# modular_expansion_system_graphics_and_so.net
KiCad netlist of a schematic drawn in EAGLE
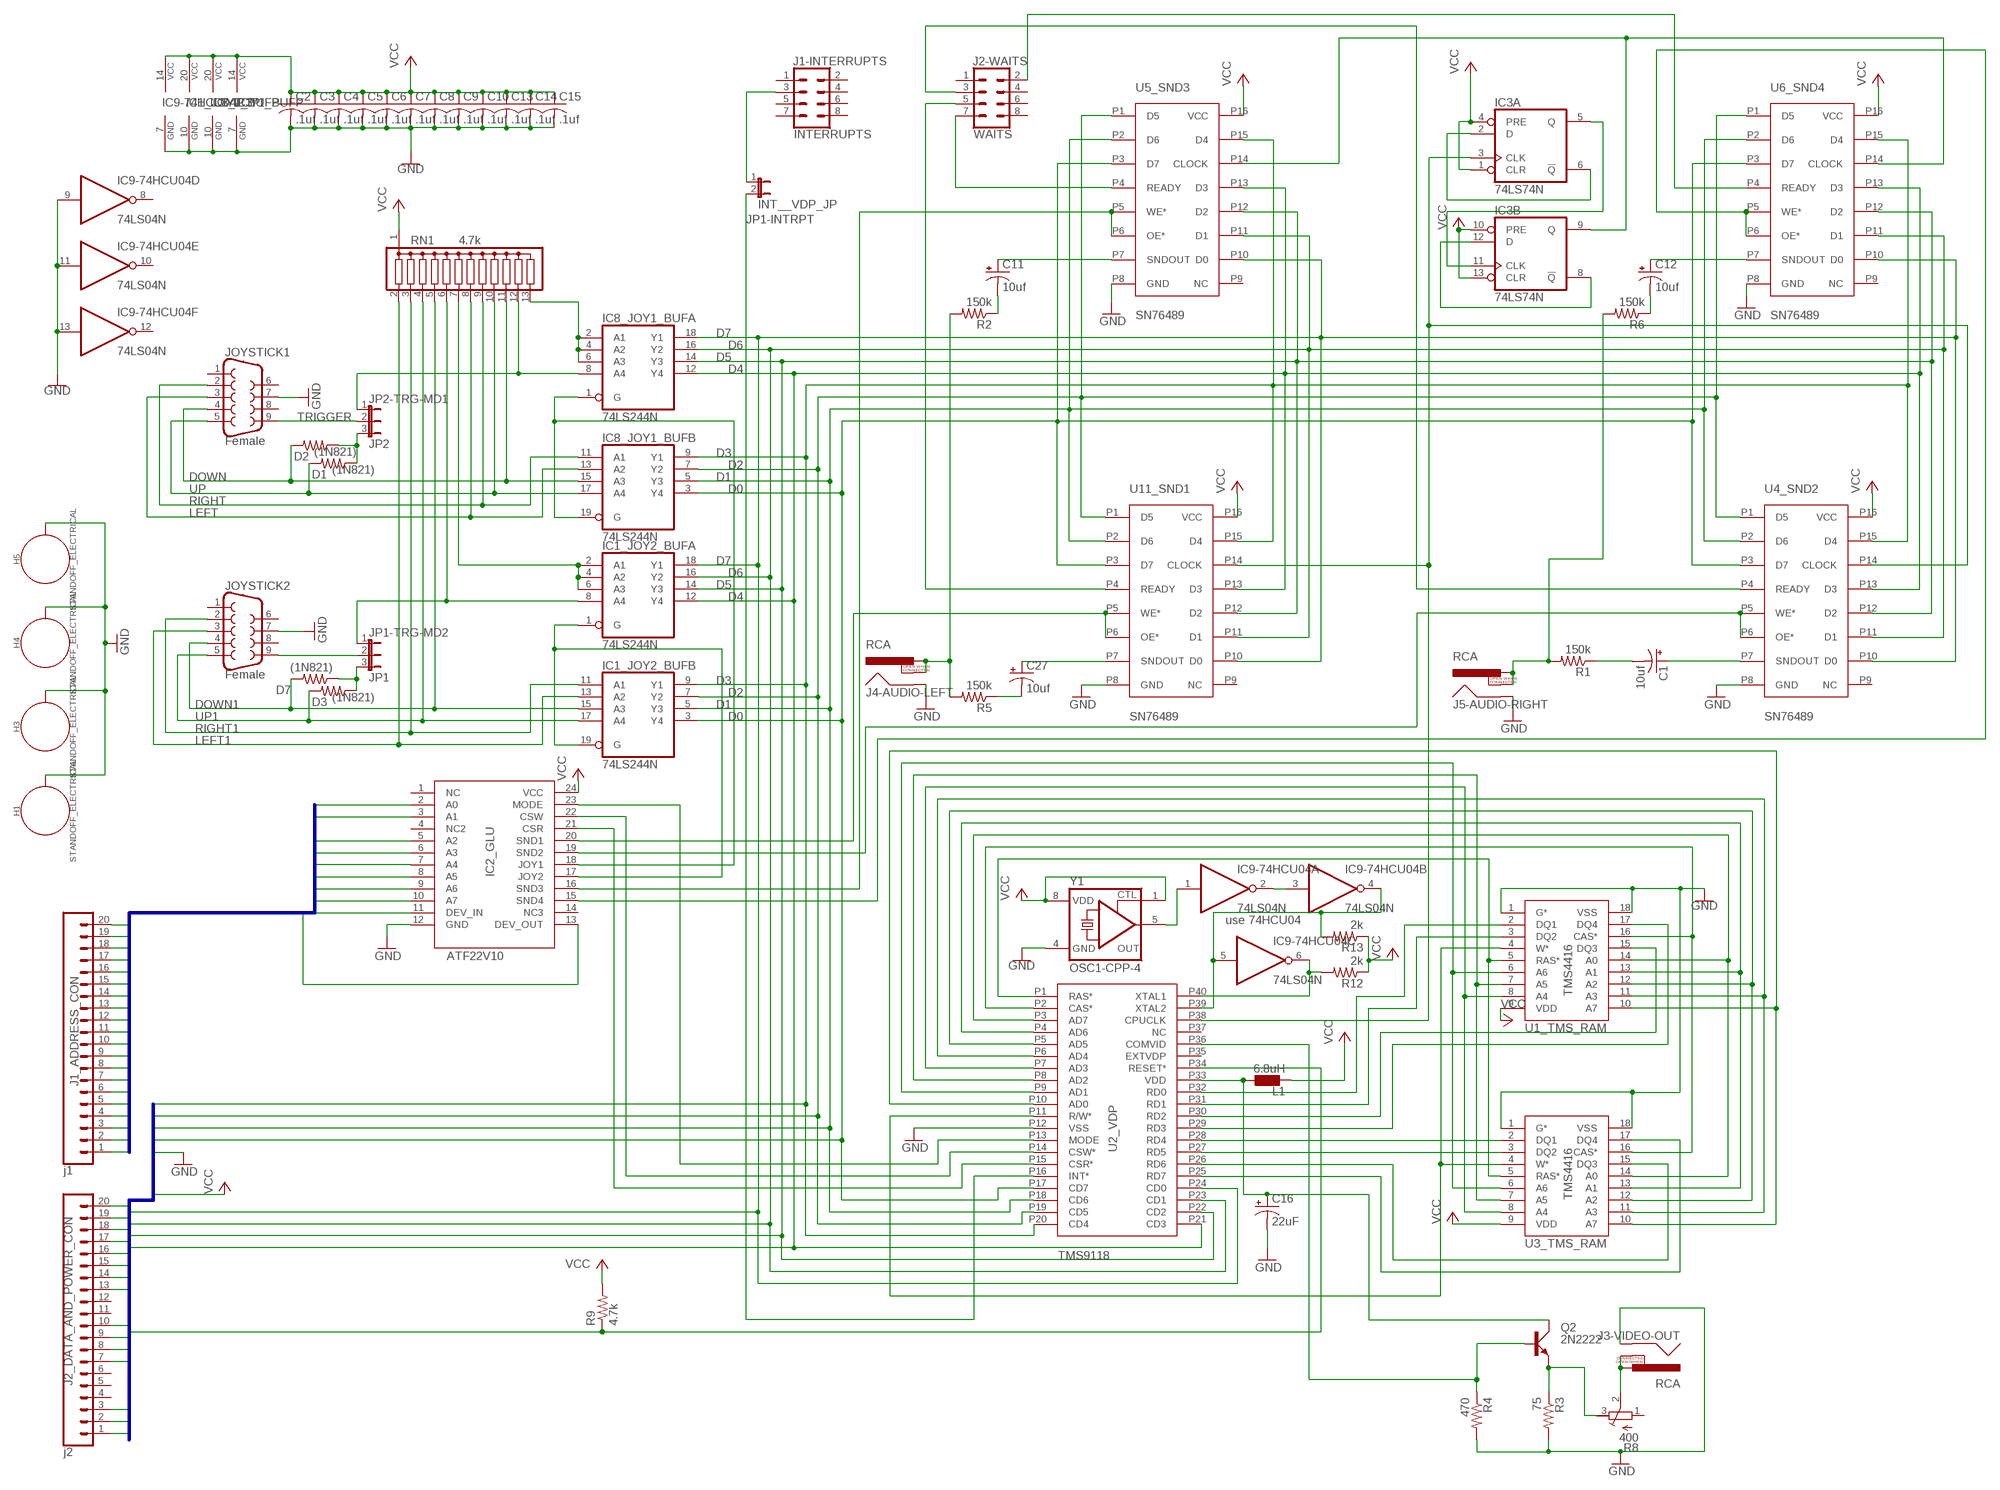
[diagram p0: schematic, sheet 1]

(export (version "E")
  (design (tool "Eeschema 10.0.6"))
  (components
    (comp (ref "C1")
      (value "10uf")
      (footprint "eagle-import:E2,5-6")
      (libsource (lib "eagle-import") (part "CPOL-USE2.5-6"))
    )
    (comp (ref "C2")
      (value ".1uf")
      (footprint "eagle-import:C025-024X044")
      (libsource (lib "eagle-import") (part "C-US025-024X044"))
    )
    (comp (ref "C3")
      (value ".1uf")
      (footprint "eagle-import:C025-024X044")
      (libsource (lib "eagle-import") (part "C-US025-024X044"))
    )
    (comp (ref "C4")
      (value ".1uf")
      (footprint "eagle-import:C025-024X044")
      (libsource (lib "eagle-import") (part "C-US025-024X044"))
    )
    (comp (ref "C5")
      (value ".1uf")
      (footprint "eagle-import:C025-024X044")
      (libsource (lib "eagle-import") (part "C-US025-024X044"))
    )
    (comp (ref "C6")
      (value ".1uf")
      (footprint "eagle-import:C025-024X044")
      (libsource (lib "eagle-import") (part "C-US025-024X044"))
    )
    (comp (ref "C7")
      (value ".1uf")
      (footprint "eagle-import:C025-024X044")
      (libsource (lib "eagle-import") (part "C-US025-024X044"))
    )
    (comp (ref "C8")
      (value ".1uf")
      (footprint "eagle-import:C025-024X044")
      (libsource (lib "eagle-import") (part "C-US025-024X044"))
    )
    (comp (ref "C9")
      (value ".1uf")
      (footprint "eagle-import:C025-024X044")
      (libsource (lib "eagle-import") (part "C-US025-024X044"))
    )
    (comp (ref "C10")
      (value ".1uf")
      (footprint "eagle-import:C025-024X044")
      (libsource (lib "eagle-import") (part "C-US025-024X044"))
    )
    (comp (ref "C11")
      (value "10uf")
      (footprint "eagle-import:E2,5-6")
      (libsource (lib "eagle-import") (part "CPOL-USE2.5-6"))
    )
    (comp (ref "C12")
      (value "10uf")
      (footprint "eagle-import:E2,5-6")
      (libsource (lib "eagle-import") (part "CPOL-USE2.5-6"))
    )
    (comp (ref "C13")
      (value ".1uf")
      (footprint "eagle-import:C025-024X044")
      (libsource (lib "eagle-import") (part "C-US025-024X044"))
    )
    (comp (ref "C14")
      (value ".1uf")
      (footprint "eagle-import:C025-024X044")
      (libsource (lib "eagle-import") (part "C-US025-024X044"))
    )
    (comp (ref "C15")
      (value ".1uf")
      (footprint "eagle-import:C025-024X044")
      (libsource (lib "eagle-import") (part "C-US025-024X044"))
    )
    (comp (ref "C16")
      (value "22uF")
      (footprint "eagle-import:E2,5-5")
      (libsource (lib "eagle-import") (part "CPOL-USE2.5-5"))
    )
    (comp (ref "C27")
      (value "10uf")
      (footprint "eagle-import:E2,5-6")
      (libsource (lib "eagle-import") (part "CPOL-USE2.5-6"))
    )
    (comp (ref "D1")
      (value "(1N821)")
      (footprint "eagle-import:0204V")
      (libsource (lib "eagle-import") (part "R-US_0204/2V"))
    )
    (comp (ref "D2")
      (value "(1N821)")
      (footprint "eagle-import:0204V")
      (libsource (lib "eagle-import") (part "R-US_0204/2V"))
    )
    (comp (ref "D3")
      (value "(1N821)")
      (footprint "eagle-import:0204V")
      (libsource (lib "eagle-import") (part "R-US_0204/2V"))
    )
    (comp (ref "D7")
      (value "(1N821)")
      (footprint "eagle-import:0204V")
      (libsource (lib "eagle-import") (part "R-US_0204/2V"))
    )
    (comp (ref "H1")
      (value "STANDOFF_ELECTRICAL")
      (footprint "eagle-import:STANDOFF-ELECTRICAL")
      (libsource (lib "eagle-import") (part "STANDOFF_ELECTRICAL"))
    )
    (comp (ref "H3")
      (value "STANDOFF_ELECTRICAL")
      (footprint "eagle-import:STANDOFF-ELECTRICAL")
      (libsource (lib "eagle-import") (part "STANDOFF_ELECTRICAL"))
    )
    (comp (ref "H4")
      (value "STANDOFF_ELECTRICAL")
      (footprint "eagle-import:STANDOFF-ELECTRICAL")
      (libsource (lib "eagle-import") (part "STANDOFF_ELECTRICAL"))
    )
    (comp (ref "H5")
      (value "STANDOFF_ELECTRICAL")
      (footprint "eagle-import:STANDOFF-ELECTRICAL")
      (libsource (lib "eagle-import") (part "STANDOFF_ELECTRICAL"))
    )
    (comp (ref "IC1_JOY2_BUF")
      (value "74LS244N")
      (footprint "eagle-import:DIL20")
      (libsource (lib "eagle-import") (part "74244NLS"))
    )
    (comp (ref "IC2_GLU")
      (value "ATF22V10")
      (footprint "eagle-import:DIP24SKI")
      (libsource (lib "eagle-import") (part "TRS80MXS_DECODER"))
    )
    (comp (ref "IC3")
      (value "74LS74N")
      (footprint "eagle-import:DIL14")
      (libsource (lib "eagle-import") (part "7474NLS"))
    )
    (comp (ref "IC8_JOY1_BUF")
      (value "74LS244N")
      (footprint "eagle-import:DIL20")
      (libsource (lib "eagle-import") (part "74244NLS"))
    )
    (comp (ref "IC9-74HCU04")
      (value "74LS04N")
      (footprint "eagle-import:DIL14")
      (libsource (lib "eagle-import") (part "7404NLS"))
    )
    (comp (ref "J1-INTERRUPTS")
      (value "INTERRUPTS")
      (footprint "eagle-import:2X4")
      (libsource (lib "eagle-import") (part "CONN_04X2"))
    )
    (comp (ref "J1_ADDRESS_CON")
      (value "j1")
      (footprint "eagle-import:1X20")
      (libsource (lib "eagle-import") (part "CONN_20"))
    )
    (comp (ref "J2-WAITS")
      (value "WAITS")
      (footprint "eagle-import:2X4")
      (libsource (lib "eagle-import") (part "CONN_04X2"))
    )
    (comp (ref "J2_DATA_AND_POWER_CON")
      (value "j2")
      (footprint "eagle-import:1X20")
      (libsource (lib "eagle-import") (part "CONN_20"))
    )
    (comp (ref "J3-VIDEO-OUT")
      (value "RCA")
      (footprint "eagle-import:RCA")
      (libsource (lib "eagle-import") (part "RCA"))
    )
    (comp (ref "J4-AUDIO-LEFT")
      (value "RCA")
      (footprint "eagle-import:RCA")
      (libsource (lib "eagle-import") (part "RCA"))
    )
    (comp (ref "J5-AUDIO-RIGHT")
      (value "RCA")
      (footprint "eagle-import:RCA")
      (libsource (lib "eagle-import") (part "RCA"))
    )
    (comp (ref "JOYSTICK1")
      (value "Female")
      (footprint "eagle-import:DB9")
      (libsource (lib "eagle-import") (part "DB9FEMALE"))
    )
    (comp (ref "JOYSTICK2")
      (value "Female")
      (footprint "eagle-import:DB9")
      (libsource (lib "eagle-import") (part "DB9FEMALE"))
    )
    (comp (ref "JP1-INTRPT")
      (value "INT__VDP_JP")
      (footprint "eagle-import:JP1")
      (libsource (lib "eagle-import") (part "JP1E"))
    )
    (comp (ref "JP1-TRG-MD2")
      (value "JP1")
      (footprint "eagle-import:JP2")
      (libsource (lib "eagle-import") (part "JP2E"))
    )
    (comp (ref "JP2-TRG-MD1")
      (value "JP2")
      (footprint "eagle-import:JP2")
      (libsource (lib "eagle-import") (part "JP2E"))
    )
    (comp (ref "L1")
      (value "6.8uH")
      (footprint "eagle-import:0207_10")
      (libsource (lib "eagle-import") (part "L0207/10"))
    )
    (comp (ref "Q2")
      (value "2N2222")
      (footprint "eagle-import:TO18A")
      (libsource (lib "eagle-import") (part "2N2222"))
    )
    (comp (ref "R1")
      (value "150k")
      (footprint "eagle-import:0207_2V")
      (libsource (lib "eagle-import") (part "resistor_348_R-US_0207/2V"))
    )
    (comp (ref "R2")
      (value "150k")
      (footprint "eagle-import:0207_2V")
      (libsource (lib "eagle-import") (part "resistor_348_R-US_0207/2V"))
    )
    (comp (ref "R3")
      (value "75")
      (footprint "eagle-import:0207_2V")
      (libsource (lib "eagle-import") (part "resistor_348_R-US_0207/2V"))
    )
    (comp (ref "R4")
      (value "470")
      (footprint "eagle-import:0207_2V")
      (libsource (lib "eagle-import") (part "resistor_348_R-US_0207/2V"))
    )
    (comp (ref "R5")
      (value "150k")
      (footprint "eagle-import:0207_2V")
      (libsource (lib "eagle-import") (part "resistor_348_R-US_0207/2V"))
    )
    (comp (ref "R6")
      (value "150k")
      (footprint "eagle-import:0207_2V")
      (libsource (lib "eagle-import") (part "resistor_348_R-US_0207/2V"))
    )
    (comp (ref "R8")
      (value "400")
      (footprint "eagle-import:RTRIM64W")
      (libsource (lib "eagle-import") (part "R-TRIMM64W"))
    )
    (comp (ref "R9")
      (value "4.7k")
      (footprint "eagle-import:0207_2V")
      (libsource (lib "eagle-import") (part "resistor_348_R-US_0207/2V"))
    )
    (comp (ref "R12")
      (value "2k")
      (footprint "eagle-import:0207_2V")
      (libsource (lib "eagle-import") (part "resistor_348_R-US_0207/2V"))
    )
    (comp (ref "R13")
      (value "2k")
      (footprint "eagle-import:0207_2V")
      (libsource (lib "eagle-import") (part "resistor_348_R-US_0207/2V"))
    )
    (comp (ref "RN1")
      (value "4.7k")
      (footprint "eagle-import:SIL13")
      (libsource (lib "eagle-import") (part "G12R"))
    )
    (comp (ref "U1_TMS_RAM")
      (value "TMS4416")
      (footprint "eagle-import:DIP18")
      (libsource (lib "eagle-import") (part "TMS4416"))
    )
    (comp (ref "U2_VDP")
      (value "TMS9118")
      (footprint "eagle-import:DIP40_MCU")
      (libsource (lib "eagle-import") (part "TMS9118"))
    )
    (comp (ref "U3_TMS_RAM")
      (value "TMS4416")
      (footprint "eagle-import:DIP18")
      (libsource (lib "eagle-import") (part "TMS4416"))
    )
    (comp (ref "U4_SND2")
      (value "SN76489")
      (footprint "eagle-import:DIP16")
      (libsource (lib "eagle-import") (part "SN76489"))
    )
    (comp (ref "U5_SND3")
      (value "SN76489")
      (footprint "eagle-import:DIP16")
      (libsource (lib "eagle-import") (part "SN76489"))
    )
    (comp (ref "U6_SND4")
      (value "SN76489")
      (footprint "eagle-import:DIP16")
      (libsource (lib "eagle-import") (part "SN76489"))
    )
    (comp (ref "U11_SND1")
      (value "SN76489")
      (footprint "eagle-import:DIP16")
      (libsource (lib "eagle-import") (part "SN76489"))
    )
    (comp (ref "Y1")
      (value "OSC1-CPP-4")
      (footprint "eagle-import:CPP-4")
      (libsource (lib "eagle-import") (part "OSC1-CPP-4"))
    )
  )
  (nets
    (net (code "1") (name "/A0") (class "Default")
      (node (ref "IC2_GLU") (pin "2") (pinfunction "A0_2") (pintype "bidirectional"))
      (node (ref "J1_ADDRESS_CON") (pin "1") (pinfunction "1_1") (pintype "passive"))
    )
    (net (code "2") (name "/A1") (class "Default")
      (node (ref "IC2_GLU") (pin "3") (pinfunction "A1_3") (pintype "bidirectional"))
      (node (ref "J1_ADDRESS_CON") (pin "2") (pinfunction "2_2") (pintype "passive"))
    )
    (net (code "3") (name "/A2") (class "Default")
      (node (ref "IC2_GLU") (pin "5") (pinfunction "A2_5") (pintype "bidirectional"))
      (node (ref "J1_ADDRESS_CON") (pin "3") (pinfunction "3_3") (pintype "passive"))
    )
    (net (code "4") (name "/A3") (class "Default")
      (node (ref "IC2_GLU") (pin "6") (pinfunction "A3_6") (pintype "bidirectional"))
      (node (ref "J1_ADDRESS_CON") (pin "4") (pinfunction "4_4") (pintype "passive"))
    )
    (net (code "5") (name "/A4") (class "Default")
      (node (ref "IC2_GLU") (pin "7") (pinfunction "A4_7") (pintype "bidirectional"))
      (node (ref "J1_ADDRESS_CON") (pin "5") (pinfunction "5_5") (pintype "passive"))
    )
    (net (code "6") (name "/A5") (class "Default")
      (node (ref "IC2_GLU") (pin "8") (pinfunction "A5_8") (pintype "bidirectional"))
      (node (ref "J1_ADDRESS_CON") (pin "6") (pinfunction "6_6") (pintype "passive"))
    )
    (net (code "7") (name "/A6") (class "Default")
      (node (ref "IC2_GLU") (pin "9") (pinfunction "A6_9") (pintype "bidirectional"))
      (node (ref "J1_ADDRESS_CON") (pin "7") (pinfunction "7_7") (pintype "passive"))
    )
    (net (code "8") (name "/A7") (class "Default")
      (node (ref "IC2_GLU") (pin "10") (pinfunction "A7_10") (pintype "bidirectional"))
      (node (ref "J1_ADDRESS_CON") (pin "8") (pinfunction "8_8") (pintype "passive"))
    )
    (net (code "9") (name "/D0") (class "Default")
      (node (ref "IC1_JOY2_BUF") (pin "3") (pinfunction "Y4_3") (pintype "tri_state"))
      (node (ref "IC8_JOY1_BUF") (pin "3") (pinfunction "Y4_3") (pintype "tri_state"))
      (node (ref "J2_DATA_AND_POWER_CON") (pin "20") (pinfunction "20_20") (pintype "passive"))
      (node (ref "U11_SND1") (pin "P3") (pinfunction "D7_P3") (pintype "bidirectional"))
      (node (ref "U2_VDP") (pin "P17") (pinfunction "CD7_P17") (pintype "bidirectional"))
      (node (ref "U4_SND2") (pin "P3") (pinfunction "D7_P3") (pintype "bidirectional"))
      (node (ref "U5_SND3") (pin "P3") (pinfunction "D7_P3") (pintype "bidirectional"))
      (node (ref "U6_SND4") (pin "P3") (pinfunction "D7_P3") (pintype "bidirectional"))
    )
    (net (code "10") (name "/D1") (class "Default")
      (node (ref "IC1_JOY2_BUF") (pin "5") (pinfunction "Y3_5") (pintype "tri_state"))
      (node (ref "IC8_JOY1_BUF") (pin "5") (pinfunction "Y3_5") (pintype "tri_state"))
      (node (ref "J2_DATA_AND_POWER_CON") (pin "19") (pinfunction "19_19") (pintype "passive"))
      (node (ref "U11_SND1") (pin "P2") (pinfunction "D6_P2") (pintype "bidirectional"))
      (node (ref "U2_VDP") (pin "P18") (pinfunction "CD6_P18") (pintype "bidirectional"))
      (node (ref "U4_SND2") (pin "P2") (pinfunction "D6_P2") (pintype "bidirectional"))
      (node (ref "U5_SND3") (pin "P2") (pinfunction "D6_P2") (pintype "bidirectional"))
      (node (ref "U6_SND4") (pin "P2") (pinfunction "D6_P2") (pintype "bidirectional"))
    )
    (net (code "11") (name "/D2") (class "Default")
      (node (ref "IC1_JOY2_BUF") (pin "7") (pinfunction "Y2_7") (pintype "tri_state"))
      (node (ref "IC8_JOY1_BUF") (pin "7") (pinfunction "Y2_7") (pintype "tri_state"))
      (node (ref "J2_DATA_AND_POWER_CON") (pin "18") (pinfunction "18_18") (pintype "passive"))
      (node (ref "U11_SND1") (pin "P1") (pinfunction "D5_P1") (pintype "bidirectional"))
      (node (ref "U2_VDP") (pin "P19") (pinfunction "CD5_P19") (pintype "bidirectional"))
      (node (ref "U4_SND2") (pin "P1") (pinfunction "D5_P1") (pintype "bidirectional"))
      (node (ref "U5_SND3") (pin "P1") (pinfunction "D5_P1") (pintype "bidirectional"))
      (node (ref "U6_SND4") (pin "P1") (pinfunction "D5_P1") (pintype "bidirectional"))
    )
    (net (code "12") (name "/D3") (class "Default")
      (node (ref "IC1_JOY2_BUF") (pin "9") (pinfunction "Y1_9") (pintype "tri_state"))
      (node (ref "IC8_JOY1_BUF") (pin "9") (pinfunction "Y1_9") (pintype "tri_state"))
      (node (ref "J2_DATA_AND_POWER_CON") (pin "17") (pinfunction "17_17") (pintype "passive"))
      (node (ref "U11_SND1") (pin "P15") (pinfunction "D4_P15") (pintype "bidirectional"))
      (node (ref "U2_VDP") (pin "P20") (pinfunction "CD4_P20") (pintype "bidirectional"))
      (node (ref "U4_SND2") (pin "P15") (pinfunction "D4_P15") (pintype "bidirectional"))
      (node (ref "U5_SND3") (pin "P15") (pinfunction "D4_P15") (pintype "bidirectional"))
      (node (ref "U6_SND4") (pin "P15") (pinfunction "D4_P15") (pintype "bidirectional"))
    )
    (net (code "13") (name "/D4") (class "Default")
      (node (ref "IC1_JOY2_BUF") (pin "12") (pinfunction "Y4_12") (pintype "tri_state"))
      (node (ref "IC8_JOY1_BUF") (pin "12") (pinfunction "Y4_12") (pintype "tri_state"))
      (node (ref "J2_DATA_AND_POWER_CON") (pin "16") (pinfunction "16_16") (pintype "passive"))
      (node (ref "U11_SND1") (pin "P13") (pinfunction "D3_P13") (pintype "bidirectional"))
      (node (ref "U2_VDP") (pin "P21") (pinfunction "CD3_P21") (pintype "bidirectional"))
      (node (ref "U4_SND2") (pin "P13") (pinfunction "D3_P13") (pintype "bidirectional"))
      (node (ref "U5_SND3") (pin "P13") (pinfunction "D3_P13") (pintype "bidirectional"))
      (node (ref "U6_SND4") (pin "P13") (pinfunction "D3_P13") (pintype "bidirectional"))
    )
    (net (code "14") (name "/D5") (class "Default")
      (node (ref "IC1_JOY2_BUF") (pin "14") (pinfunction "Y3_14") (pintype "tri_state"))
      (node (ref "IC8_JOY1_BUF") (pin "14") (pinfunction "Y3_14") (pintype "tri_state"))
      (node (ref "J2_DATA_AND_POWER_CON") (pin "15") (pinfunction "15_15") (pintype "passive"))
      (node (ref "U11_SND1") (pin "P12") (pinfunction "D2_P12") (pintype "bidirectional"))
      (node (ref "U2_VDP") (pin "P22") (pinfunction "CD2_P22") (pintype "bidirectional"))
      (node (ref "U4_SND2") (pin "P12") (pinfunction "D2_P12") (pintype "bidirectional"))
      (node (ref "U5_SND3") (pin "P12") (pinfunction "D2_P12") (pintype "bidirectional"))
      (node (ref "U6_SND4") (pin "P12") (pinfunction "D2_P12") (pintype "bidirectional"))
    )
    (net (code "15") (name "/D6") (class "Default")
      (node (ref "IC1_JOY2_BUF") (pin "16") (pinfunction "Y2_16") (pintype "tri_state"))
      (node (ref "IC8_JOY1_BUF") (pin "16") (pinfunction "Y2_16") (pintype "tri_state"))
      (node (ref "J2_DATA_AND_POWER_CON") (pin "14") (pinfunction "14_14") (pintype "passive"))
      (node (ref "U11_SND1") (pin "P11") (pinfunction "D1_P11") (pintype "bidirectional"))
      (node (ref "U2_VDP") (pin "P23") (pinfunction "CD1_P23") (pintype "bidirectional"))
      (node (ref "U4_SND2") (pin "P11") (pinfunction "D1_P11") (pintype "bidirectional"))
      (node (ref "U5_SND3") (pin "P11") (pinfunction "D1_P11") (pintype "bidirectional"))
      (node (ref "U6_SND4") (pin "P11") (pinfunction "D1_P11") (pintype "bidirectional"))
    )
    (net (code "16") (name "/D7") (class "Default")
      (node (ref "IC1_JOY2_BUF") (pin "18") (pinfunction "Y1_18") (pintype "tri_state"))
      (node (ref "IC8_JOY1_BUF") (pin "18") (pinfunction "Y1_18") (pintype "tri_state"))
      (node (ref "J2_DATA_AND_POWER_CON") (pin "13") (pinfunction "13_13") (pintype "passive"))
      (node (ref "U11_SND1") (pin "P10") (pinfunction "D0_P10") (pintype "bidirectional"))
      (node (ref "U2_VDP") (pin "P24") (pinfunction "CD0_P24") (pintype "bidirectional"))
      (node (ref "U4_SND2") (pin "P10") (pinfunction "D0_P10") (pintype "bidirectional"))
      (node (ref "U5_SND3") (pin "P10") (pinfunction "D0_P10") (pintype "bidirectional"))
      (node (ref "U6_SND4") (pin "P10") (pinfunction "D0_P10") (pintype "bidirectional"))
    )
    (net (code "17") (name "/DOWN") (class "Default")
      (node (ref "D2") (pin "2") (pinfunction "2_2") (pintype "passive"))
      (node (ref "IC8_JOY1_BUF") (pin "15") (pinfunction "A3_15") (pintype "input"))
      (node (ref "JOYSTICK1") (pin "4") (pinfunction "4_4") (pintype "passive"))
      (node (ref "RN1") (pin "11") (pinfunction "11_11") (pintype "passive"))
    )
    (net (code "18") (name "/DOWN1") (class "Default")
      (node (ref "D7") (pin "2") (pinfunction "2_2") (pintype "passive"))
      (node (ref "IC1_JOY2_BUF") (pin "15") (pinfunction "A3_15") (pintype "input"))
      (node (ref "JOYSTICK2") (pin "4") (pinfunction "4_4") (pintype "passive"))
      (node (ref "RN1") (pin "5") (pinfunction "5_5") (pintype "passive"))
    )
    (net (code "19") (name "/IN*") (class "Default")
      (node (ref "IC2_GLU") (pin "11") (pinfunction "DEV_IN_11") (pintype "bidirectional"))
      (node (ref "J1_ADDRESS_CON") (pin "17") (pinfunction "17_17") (pintype "passive"))
    )
    (net (code "20") (name "/LEFT") (class "Default")
      (node (ref "IC8_JOY1_BUF") (pin "13") (pinfunction "A2_13") (pintype "input"))
      (node (ref "JOYSTICK1") (pin "3") (pinfunction "3_3") (pintype "passive"))
      (node (ref "RN1") (pin "8") (pinfunction "8_8") (pintype "passive"))
    )
    (net (code "21") (name "/LEFT1") (class "Default")
      (node (ref "IC1_JOY2_BUF") (pin "13") (pinfunction "A2_13") (pintype "input"))
      (node (ref "JOYSTICK2") (pin "3") (pinfunction "3_3") (pintype "passive"))
      (node (ref "RN1") (pin "2") (pinfunction "2_2") (pintype "passive"))
    )
    (net (code "22") (name "/OUT*") (class "Default")
      (node (ref "IC2_GLU") (pin "13") (pinfunction "DEV_OUT_13") (pintype "bidirectional"))
      (node (ref "J1_ADDRESS_CON") (pin "18") (pinfunction "18_18") (pintype "passive"))
    )
    (net (code "23") (name "/RIGHT") (class "Default")
      (node (ref "IC8_JOY1_BUF") (pin "11") (pinfunction "A1_11") (pintype "input"))
      (node (ref "JOYSTICK1") (pin "2") (pinfunction "2_2") (pintype "passive"))
      (node (ref "RN1") (pin "9") (pinfunction "9_9") (pintype "passive"))
    )
    (net (code "24") (name "/RIGHT1") (class "Default")
      (node (ref "IC1_JOY2_BUF") (pin "11") (pinfunction "A1_11") (pintype "input"))
      (node (ref "JOYSTICK2") (pin "2") (pinfunction "2_2") (pintype "passive"))
      (node (ref "RN1") (pin "3") (pinfunction "3_3") (pintype "passive"))
    )
    (net (code "25") (name "/SYSRES*") (class "Default")
      (node (ref "J2_DATA_AND_POWER_CON") (pin "8") (pinfunction "8_8") (pintype "passive"))
      (node (ref "R9") (pin "1") (pinfunction "1_1") (pintype "passive"))
      (node (ref "U2_VDP") (pin "P34") (pinfunction "RESET*_P34") (pintype "bidirectional"))
    )
    (net (code "26") (name "/TRIGGER") (class "Default")
      (node (ref "JOYSTICK1") (pin "9") (pinfunction "9_9") (pintype "passive"))
      (node (ref "JP2-TRG-MD1") (pin "2") (pinfunction "2_2") (pintype "passive"))
    )
    (net (code "27") (name "/UP") (class "Default")
      (node (ref "D1") (pin "2") (pinfunction "2_2") (pintype "passive"))
      (node (ref "IC8_JOY1_BUF") (pin "17") (pinfunction "A4_17") (pintype "input"))
      (node (ref "JOYSTICK1") (pin "5") (pinfunction "5_5") (pintype "passive"))
      (node (ref "RN1") (pin "10") (pinfunction "10_10") (pintype "passive"))
    )
    (net (code "28") (name "/UP1") (class "Default")
      (node (ref "D3") (pin "2") (pinfunction "2_2") (pintype "passive"))
      (node (ref "IC1_JOY2_BUF") (pin "17") (pinfunction "A4_17") (pintype "input"))
      (node (ref "JOYSTICK2") (pin "5") (pinfunction "5_5") (pintype "passive"))
      (node (ref "RN1") (pin "4") (pinfunction "4_4") (pintype "passive"))
    )
    (net (code "29") (name "GND") (class "Default")
      (node (ref "C10") (pin "2") (pinfunction "2_2") (pintype "passive"))
      (node (ref "C13") (pin "2") (pinfunction "2_2") (pintype "passive"))
      (node (ref "C14") (pin "2") (pinfunction "2_2") (pintype "passive"))
      (node (ref "C15") (pin "2") (pinfunction "2_2") (pintype "passive"))
      (node (ref "C16") (pin "-") (pinfunction "-_-") (pintype "passive"))
      (node (ref "C2") (pin "2") (pinfunction "2_2") (pintype "passive"))
      (node (ref "C3") (pin "2") (pinfunction "2_2") (pintype "passive"))
      (node (ref "C4") (pin "2") (pinfunction "2_2") (pintype "passive"))
      (node (ref "C5") (pin "2") (pinfunction "2_2") (pintype "passive"))
      (node (ref "C6") (pin "2") (pinfunction "2_2") (pintype "passive"))
      (node (ref "C7") (pin "2") (pinfunction "2_2") (pintype "passive"))
      (node (ref "C8") (pin "2") (pinfunction "2_2") (pintype "passive"))
      (node (ref "C9") (pin "2") (pinfunction "2_2") (pintype "passive"))
      (node (ref "H1") (pin "P1") (pinfunction "P$1_P1") (pintype "bidirectional"))
      (node (ref "H3") (pin "P1") (pinfunction "P$1_P1") (pintype "bidirectional"))
      (node (ref "H4") (pin "P1") (pinfunction "P$1_P1") (pintype "bidirectional"))
      (node (ref "H5") (pin "P1") (pinfunction "P$1_P1") (pintype "bidirectional"))
      (node (ref "IC1_JOY2_BUF") (pin "10") (pinfunction "GND_10") (pintype "power_in"))
      (node (ref "IC2_GLU") (pin "12") (pinfunction "GND_12") (pintype "bidirectional"))
      (node (ref "IC3") (pin "7") (pinfunction "GND_7") (pintype "power_in"))
      (node (ref "IC8_JOY1_BUF") (pin "10") (pinfunction "GND_10") (pintype "power_in"))
      (node (ref "IC9-74HCU04") (pin "11") (pinfunction "I_11") (pintype "input"))
      (node (ref "IC9-74HCU04") (pin "13") (pinfunction "I_13") (pintype "input"))
      (node (ref "IC9-74HCU04") (pin "7") (pinfunction "GND_7") (pintype "power_in"))
      (node (ref "IC9-74HCU04") (pin "9") (pinfunction "I_9") (pintype "input"))
      (node (ref "J2_DATA_AND_POWER_CON") (pin "2") (pinfunction "2_2") (pintype "passive"))
      (node (ref "J3-VIDEO-OUT") (pin "SHELL") (pinfunction "SHELL_SHELL") (pintype "bidirectional"))
      (node (ref "J4-AUDIO-LEFT") (pin "SHELL") (pinfunction "SHELL_SHELL") (pintype "bidirectional"))
      (node (ref "J5-AUDIO-RIGHT") (pin "SHELL") (pinfunction "SHELL_SHELL") (pintype "bidirectional"))
      (node (ref "JOYSTICK1") (pin "7") (pinfunction "7_7") (pintype "passive"))
      (node (ref "JOYSTICK2") (pin "7") (pinfunction "7_7") (pintype "passive"))
      (node (ref "R3") (pin "2") (pinfunction "2_2") (pintype "passive"))
      (node (ref "R4") (pin "2") (pinfunction "2_2") (pintype "passive"))
      (node (ref "U11_SND1") (pin "P8") (pinfunction "GND_P8") (pintype "bidirectional"))
      (node (ref "U1_TMS_RAM") (pin "1") (pinfunction "G*_1") (pintype "bidirectional"))
      (node (ref "U1_TMS_RAM") (pin "18") (pinfunction "VSS_18") (pintype "bidirectional"))
      (node (ref "U2_VDP") (pin "P12") (pinfunction "VSS_P12") (pintype "bidirectional"))
      (node (ref "U3_TMS_RAM") (pin "1") (pinfunction "G*_1") (pintype "bidirectional"))
      (node (ref "U3_TMS_RAM") (pin "18") (pinfunction "VSS_18") (pintype "bidirectional"))
      (node (ref "U4_SND2") (pin "P8") (pinfunction "GND_P8") (pintype "bidirectional"))
      (node (ref "U5_SND3") (pin "P8") (pinfunction "GND_P8") (pintype "bidirectional"))
      (node (ref "U6_SND4") (pin "P8") (pinfunction "GND_P8") (pintype "bidirectional"))
      (node (ref "Y1") (pin "4") (pinfunction "GND_4") (pintype "power_in"))
    )
    (net (code "30") (name "Net-(C1-Pad-)") (class "Default")
      (node (ref "C1") (pin "-") (pinfunction "-_-") (pintype "passive"))
      (node (ref "R1") (pin "1") (pinfunction "1_1") (pintype "passive"))
    )
    (net (code "31") (name "Net-(C11-Pad-)") (class "Default")
      (node (ref "C11") (pin "-") (pinfunction "-_-") (pintype "passive"))
      (node (ref "R2") (pin "1") (pinfunction "1_1") (pintype "passive"))
    )
    (net (code "32") (name "Net-(C12-Pad-)") (class "Default")
      (node (ref "C12") (pin "-") (pinfunction "-_-") (pintype "passive"))
      (node (ref "R6") (pin "1") (pinfunction "1_1") (pintype "passive"))
    )
    (net (code "33") (name "Net-(C27-Pad-)") (class "Default")
      (node (ref "C27") (pin "-") (pinfunction "-_-") (pintype "passive"))
      (node (ref "R5") (pin "1") (pinfunction "1_1") (pintype "passive"))
    )
    (net (code "34") (name "Net-(D1-Pad1)") (class "Default")
      (node (ref "D1") (pin "1") (pinfunction "1_1") (pintype "passive"))
      (node (ref "D2") (pin "1") (pinfunction "1_1") (pintype "passive"))
      (node (ref "JP2-TRG-MD1") (pin "3") (pinfunction "3_3") (pintype "passive"))
    )
    (net (code "35") (name "Net-(D3-Pad1)") (class "Default")
      (node (ref "D3") (pin "1") (pinfunction "1_1") (pintype "passive"))
      (node (ref "D7") (pin "1") (pinfunction "1_1") (pintype "passive"))
      (node (ref "JP1-TRG-MD2") (pin "3") (pinfunction "3_3") (pintype "passive"))
    )
    (net (code "36") (name "Net-(IC1_JOY2_BUFA-A1)") (class "Default")
      (node (ref "IC1_JOY2_BUF") (pin "2") (pinfunction "A1_2") (pintype "input"))
      (node (ref "IC1_JOY2_BUF") (pin "4") (pinfunction "A2_4") (pintype "input"))
      (node (ref "IC1_JOY2_BUF") (pin "6") (pinfunction "A3_6") (pintype "input"))
      (node (ref "RN1") (pin "7") (pinfunction "7_7") (pintype "passive"))
    )
    (net (code "37") (name "Net-(IC1_JOY2_BUFA-A4)") (class "Default")
      (node (ref "IC1_JOY2_BUF") (pin "8") (pinfunction "A4_8") (pintype "input"))
      (node (ref "JP1-TRG-MD2") (pin "1") (pinfunction "1_1") (pintype "passive"))
      (node (ref "RN1") (pin "6") (pinfunction "6_6") (pintype "passive"))
    )
    (net (code "38") (name "Net-(IC1_JOY2_BUFA-G)") (class "Default")
      (node (ref "IC1_JOY2_BUF") (pin "1") (pinfunction "G_1") (pintype "input"))
      (node (ref "IC1_JOY2_BUF") (pin "19") (pinfunction "G_19") (pintype "input"))
      (node (ref "IC2_GLU") (pin "17") (pinfunction "JOY2_17") (pintype "bidirectional"))
    )
    (net (code "39") (name "Net-(IC2_GLU-CSR)") (class "Default")
      (node (ref "IC2_GLU") (pin "21") (pinfunction "CSR_21") (pintype "bidirectional"))
      (node (ref "U2_VDP") (pin "P15") (pinfunction "CSR*_P15") (pintype "bidirectional"))
    )
    (net (code "40") (name "Net-(IC2_GLU-CSW)") (class "Default")
      (node (ref "IC2_GLU") (pin "22") (pinfunction "CSW_22") (pintype "bidirectional"))
      (node (ref "U2_VDP") (pin "P14") (pinfunction "CSW*_P14") (pintype "bidirectional"))
    )
    (net (code "41") (name "Net-(IC2_GLU-JOY1)") (class "Default")
      (node (ref "IC2_GLU") (pin "18") (pinfunction "JOY1_18") (pintype "bidirectional"))
      (node (ref "IC8_JOY1_BUF") (pin "1") (pinfunction "G_1") (pintype "input"))
      (node (ref "IC8_JOY1_BUF") (pin "19") (pinfunction "G_19") (pintype "input"))
    )
    (net (code "42") (name "Net-(IC2_GLU-MODE)") (class "Default")
      (node (ref "IC2_GLU") (pin "23") (pinfunction "MODE_23") (pintype "bidirectional"))
      (node (ref "U2_VDP") (pin "P13") (pinfunction "MODE_P13") (pintype "bidirectional"))
    )
    (net (code "43") (name "Net-(IC2_GLU-SND1)") (class "Default")
      (node (ref "IC2_GLU") (pin "20") (pinfunction "SND1_20") (pintype "bidirectional"))
      (node (ref "U11_SND1") (pin "P5") (pinfunction "WE*_P5") (pintype "bidirectional"))
      (node (ref "U11_SND1") (pin "P6") (pinfunction "OE*_P6") (pintype "bidirectional"))
    )
    (net (code "44") (name "Net-(IC2_GLU-SND2)") (class "Default")
      (node (ref "IC2_GLU") (pin "19") (pinfunction "SND2_19") (pintype "bidirectional"))
      (node (ref "U4_SND2") (pin "P5") (pinfunction "WE*_P5") (pintype "bidirectional"))
      (node (ref "U4_SND2") (pin "P6") (pinfunction "OE*_P6") (pintype "bidirectional"))
    )
    (net (code "45") (name "Net-(IC2_GLU-SND3)") (class "Default")
      (node (ref "IC2_GLU") (pin "16") (pinfunction "SND3_16") (pintype "bidirectional"))
      (node (ref "U5_SND3") (pin "P5") (pinfunction "WE*_P5") (pintype "bidirectional"))
      (node (ref "U5_SND3") (pin "P6") (pinfunction "OE*_P6") (pintype "bidirectional"))
    )
    (net (code "46") (name "Net-(IC2_GLU-SND4)") (class "Default")
      (node (ref "IC2_GLU") (pin "15") (pinfunction "SND4_15") (pintype "bidirectional"))
      (node (ref "U6_SND4") (pin "P5") (pinfunction "WE*_P5") (pintype "bidirectional"))
      (node (ref "U6_SND4") (pin "P6") (pinfunction "OE*_P6") (pintype "bidirectional"))
    )
    (net (code "47") (name "Net-(IC3A-CLK)") (class "Default")
      (node (ref "IC3") (pin "3") (pinfunction "CLK_3") (pintype "input"))
      (node (ref "U11_SND1") (pin "P14") (pinfunction "CLOCK_P14") (pintype "bidirectional"))
      (node (ref "U2_VDP") (pin "P38") (pinfunction "CPUCLK_P38") (pintype "bidirectional"))
      (node (ref "U4_SND2") (pin "P14") (pinfunction "CLOCK_P14") (pintype "bidirectional"))
    )
    (net (code "48") (name "Net-(IC3A-D)") (class "Default")
      (node (ref "IC3") (pin "2") (pinfunction "D_2") (pintype "input"))
      (node (ref "IC3") (pin "6") (pinfunction "~{Q}_6") (pintype "output"))
    )
    (net (code "49") (name "Net-(IC3A-Q)") (class "Default")
      (node (ref "IC3") (pin "11") (pinfunction "CLK_11") (pintype "input"))
      (node (ref "IC3") (pin "5") (pinfunction "Q_5") (pintype "output"))
    )
    (net (code "50") (name "Net-(IC3B-D)") (class "Default")
      (node (ref "IC3") (pin "12") (pinfunction "D_12") (pintype "input"))
      (node (ref "IC3") (pin "8") (pinfunction "~{Q}_8") (pintype "output"))
    )
    (net (code "51") (name "Net-(IC3B-Q)") (class "Default")
      (node (ref "IC3") (pin "9") (pinfunction "Q_9") (pintype "output"))
      (node (ref "U5_SND3") (pin "P14") (pinfunction "CLOCK_P14") (pintype "bidirectional"))
      (node (ref "U6_SND4") (pin "P14") (pinfunction "CLOCK_P14") (pintype "bidirectional"))
    )
    (net (code "52") (name "Net-(IC8_JOY1_BUFA-A1)") (class "Default")
      (node (ref "IC8_JOY1_BUF") (pin "2") (pinfunction "A1_2") (pintype "input"))
      (node (ref "IC8_JOY1_BUF") (pin "4") (pinfunction "A2_4") (pintype "input"))
      (node (ref "IC8_JOY1_BUF") (pin "6") (pinfunction "A3_6") (pintype "input"))
      (node (ref "RN1") (pin "13") (pinfunction "13_13") (pintype "passive"))
    )
    (net (code "53") (name "Net-(IC8_JOY1_BUFA-A4)") (class "Default")
      (node (ref "IC8_JOY1_BUF") (pin "8") (pinfunction "A4_8") (pintype "input"))
      (node (ref "JP2-TRG-MD1") (pin "1") (pinfunction "1_1") (pintype "passive"))
      (node (ref "RN1") (pin "12") (pinfunction "12_12") (pintype "passive"))
    )
    (net (code "54") (name "Net-(IC9-74HCU04A-I)") (class "Default")
      (node (ref "IC9-74HCU04") (pin "1") (pinfunction "I_1") (pintype "input"))
      (node (ref "Y1") (pin "5") (pinfunction "OUT_5") (pintype "output"))
    )
    (net (code "55") (name "Net-(IC9-74HCU04A-O)") (class "Default")
      (node (ref "IC9-74HCU04") (pin "2") (pinfunction "O_2") (pintype "output"))
      (node (ref "IC9-74HCU04") (pin "3") (pinfunction "I_3") (pintype "input"))
    )
    (net (code "56") (name "Net-(IC9-74HCU04B-O)") (class "Default")
      (node (ref "IC9-74HCU04") (pin "4") (pinfunction "O_4") (pintype "output"))
      (node (ref "IC9-74HCU04") (pin "5") (pinfunction "I_5") (pintype "input"))
      (node (ref "R13") (pin "2") (pinfunction "2_2") (pintype "passive"))
      (node (ref "U2_VDP") (pin "P39") (pinfunction "XTAL2_P39") (pintype "bidirectional"))
    )
    (net (code "57") (name "Net-(IC9-74HCU04C-O)") (class "Default")
      (node (ref "IC9-74HCU04") (pin "6") (pinfunction "O_6") (pintype "output"))
      (node (ref "R12") (pin "2") (pinfunction "2_2") (pintype "passive"))
      (node (ref "U2_VDP") (pin "P40") (pinfunction "XTAL1_P40") (pintype "bidirectional"))
    )
    (net (code "58") (name "Net-(J1-INTERRUPTS-Pad3)") (class "Default")
      (node (ref "J1-INTERRUPTS") (pin "3") (pinfunction "3_3") (pintype "passive"))
      (node (ref "JP1-INTRPT") (pin "1") (pinfunction "1_1") (pintype "passive"))
    )
    (net (code "59") (name "Net-(J4-AUDIO-LEFT-PadPIN)") (class "Default")
      (node (ref "J4-AUDIO-LEFT") (pin "PIN") (pinfunction "PIN_PIN") (pintype "bidirectional"))
      (node (ref "J4-AUDIO-LEFT") (pin "SWITCH") (pinfunction "SWITCH_SWITCH") (pintype "bidirectional"))
      (node (ref "R2") (pin "2") (pinfunction "2_2") (pintype "passive"))
      (node (ref "R5") (pin "2") (pinfunction "2_2") (pintype "passive"))
    )
    (net (code "60") (name "Net-(J5-AUDIO-RIGHT-PadPIN)") (class "Default")
      (node (ref "J5-AUDIO-RIGHT") (pin "PIN") (pinfunction "PIN_PIN") (pintype "bidirectional"))
      (node (ref "J5-AUDIO-RIGHT") (pin "SWITCH") (pinfunction "SWITCH_SWITCH") (pintype "bidirectional"))
      (node (ref "R1") (pin "2") (pinfunction "2_2") (pintype "passive"))
      (node (ref "R6") (pin "2") (pinfunction "2_2") (pintype "passive"))
    )
    (net (code "61") (name "Net-(JOYSTICK2-Pad9)") (class "Default")
      (node (ref "JOYSTICK2") (pin "9") (pinfunction "9_9") (pintype "passive"))
      (node (ref "JP1-TRG-MD2") (pin "2") (pinfunction "2_2") (pintype "passive"))
    )
    (net (code "62") (name "Net-(R8-E)") (class "Default")
      (node (ref "Q2") (pin "E") (pinfunction "E_E") (pintype "passive"))
      (node (ref "R3") (pin "1") (pinfunction "1_1") (pintype "passive"))
      (node (ref "R8") (pin "3") (pinfunction "E_3") (pintype "passive"))
    )
    (net (code "63") (name "Net-(R8-S)") (class "Default")
      (node (ref "J3-VIDEO-OUT") (pin "PIN") (pinfunction "PIN_PIN") (pintype "bidirectional"))
      (node (ref "J3-VIDEO-OUT") (pin "SWITCH") (pinfunction "SWITCH_SWITCH") (pintype "bidirectional"))
      (node (ref "R8") (pin "2") (pinfunction "S_2") (pintype "passive"))
    )
    (net (code "64") (name "Net-(U1_TMS_RAM-A0)") (class "Default")
      (node (ref "U1_TMS_RAM") (pin "14") (pinfunction "A0_14") (pintype "bidirectional"))
      (node (ref "U2_VDP") (pin "P3") (pinfunction "AD7_P3") (pintype "bidirectional"))
      (node (ref "U3_TMS_RAM") (pin "14") (pinfunction "A0_14") (pintype "bidirectional"))
    )
    (net (code "65") (name "Net-(U1_TMS_RAM-A1)") (class "Default")
      (node (ref "U1_TMS_RAM") (pin "13") (pinfunction "A1_13") (pintype "bidirectional"))
      (node (ref "U2_VDP") (pin "P4") (pinfunction "AD6_P4") (pintype "bidirectional"))
      (node (ref "U3_TMS_RAM") (pin "13") (pinfunction "A1_13") (pintype "bidirectional"))
    )
    (net (code "66") (name "Net-(U1_TMS_RAM-A2)") (class "Default")
      (node (ref "U1_TMS_RAM") (pin "12") (pinfunction "A2_12") (pintype "bidirectional"))
      (node (ref "U2_VDP") (pin "P5") (pinfunction "AD5_P5") (pintype "bidirectional"))
      (node (ref "U3_TMS_RAM") (pin "12") (pinfunction "A2_12") (pintype "bidirectional"))
    )
    (net (code "67") (name "Net-(U1_TMS_RAM-A3)") (class "Default")
      (node (ref "U1_TMS_RAM") (pin "11") (pinfunction "A3_11") (pintype "bidirectional"))
      (node (ref "U2_VDP") (pin "P6") (pinfunction "AD4_P6") (pintype "bidirectional"))
      (node (ref "U3_TMS_RAM") (pin "11") (pinfunction "A3_11") (pintype "bidirectional"))
    )
    (net (code "68") (name "Net-(U1_TMS_RAM-A4)") (class "Default")
      (node (ref "U1_TMS_RAM") (pin "8") (pinfunction "A4_8") (pintype "bidirectional"))
      (node (ref "U2_VDP") (pin "P7") (pinfunction "AD3_P7") (pintype "bidirectional"))
      (node (ref "U3_TMS_RAM") (pin "8") (pinfunction "A4_8") (pintype "bidirectional"))
    )
    (net (code "69") (name "Net-(U1_TMS_RAM-A5)") (class "Default")
      (node (ref "U1_TMS_RAM") (pin "7") (pinfunction "A5_7") (pintype "bidirectional"))
      (node (ref "U2_VDP") (pin "P8") (pinfunction "AD2_P8") (pintype "bidirectional"))
      (node (ref "U3_TMS_RAM") (pin "7") (pinfunction "A5_7") (pintype "bidirectional"))
    )
    (net (code "70") (name "Net-(U1_TMS_RAM-A6)") (class "Default")
      (node (ref "U1_TMS_RAM") (pin "6") (pinfunction "A6_6") (pintype "bidirectional"))
      (node (ref "U2_VDP") (pin "P9") (pinfunction "AD1_P9") (pintype "bidirectional"))
      (node (ref "U3_TMS_RAM") (pin "6") (pinfunction "A6_6") (pintype "bidirectional"))
    )
    (net (code "71") (name "Net-(U1_TMS_RAM-A7)") (class "Default")
      (node (ref "U1_TMS_RAM") (pin "10") (pinfunction "A7_10") (pintype "bidirectional"))
      (node (ref "U2_VDP") (pin "P10") (pinfunction "AD0_P10") (pintype "bidirectional"))
      (node (ref "U3_TMS_RAM") (pin "10") (pinfunction "A7_10") (pintype "bidirectional"))
    )
    (net (code "72") (name "Net-(U1_TMS_RAM-CAS*)") (class "Default")
      (node (ref "U1_TMS_RAM") (pin "16") (pinfunction "CAS*_16") (pintype "bidirectional"))
      (node (ref "U2_VDP") (pin "P2") (pinfunction "CAS*_P2") (pintype "bidirectional"))
      (node (ref "U3_TMS_RAM") (pin "16") (pinfunction "CAS*_16") (pintype "bidirectional"))
    )
    (net (code "73") (name "Net-(U1_TMS_RAM-DQ1)") (class "Default")
      (node (ref "U1_TMS_RAM") (pin "2") (pinfunction "DQ1_2") (pintype "bidirectional"))
      (node (ref "U2_VDP") (pin "P32") (pinfunction "RD0_P32") (pintype "bidirectional"))
    )
    (net (code "74") (name "Net-(U1_TMS_RAM-DQ2)") (class "Default")
      (node (ref "U1_TMS_RAM") (pin "3") (pinfunction "DQ2_3") (pintype "bidirectional"))
      (node (ref "U2_VDP") (pin "P31") (pinfunction "RD1_P31") (pintype "bidirectional"))
    )
    (net (code "75") (name "Net-(U1_TMS_RAM-DQ3)") (class "Default")
      (node (ref "U1_TMS_RAM") (pin "15") (pinfunction "DQ3_15") (pintype "bidirectional"))
      (node (ref "U2_VDP") (pin "P30") (pinfunction "RD2_P30") (pintype "bidirectional"))
    )
    (net (code "76") (name "Net-(U1_TMS_RAM-DQ4)") (class "Default")
      (node (ref "U1_TMS_RAM") (pin "17") (pinfunction "DQ4_17") (pintype "bidirectional"))
      (node (ref "U2_VDP") (pin "P29") (pinfunction "RD3_P29") (pintype "bidirectional"))
    )
    (net (code "77") (name "Net-(U1_TMS_RAM-RAS*)") (class "Default")
      (node (ref "U1_TMS_RAM") (pin "5") (pinfunction "RAS*_5") (pintype "bidirectional"))
      (node (ref "U2_VDP") (pin "P1") (pinfunction "RAS*_P1") (pintype "bidirectional"))
      (node (ref "U3_TMS_RAM") (pin "5") (pinfunction "RAS*_5") (pintype "bidirectional"))
    )
    (net (code "78") (name "Net-(U1_TMS_RAM-W*)") (class "Default")
      (node (ref "U1_TMS_RAM") (pin "4") (pinfunction "W*_4") (pintype "bidirectional"))
      (node (ref "U2_VDP") (pin "P11") (pinfunction "R/W*_P11") (pintype "bidirectional"))
      (node (ref "U3_TMS_RAM") (pin "4") (pinfunction "W*_4") (pintype "bidirectional"))
    )
    (net (code "79") (name "Net-(U2_VDP-COMVID)") (class "Default")
      (node (ref "Q2") (pin "B") (pinfunction "B_B") (pintype "passive"))
      (node (ref "R4") (pin "1") (pinfunction "1_1") (pintype "passive"))
      (node (ref "U2_VDP") (pin "P36") (pinfunction "COMVID_P36") (pintype "bidirectional"))
    )
    (net (code "80") (name "Net-(U2_VDP-INT*)") (class "Default")
      (node (ref "JP1-INTRPT") (pin "2") (pinfunction "2_2") (pintype "passive"))
      (node (ref "U2_VDP") (pin "P16") (pinfunction "INT*_P16") (pintype "bidirectional"))
    )
    (net (code "81") (name "Net-(U2_VDP-RD4)") (class "Default")
      (node (ref "U2_VDP") (pin "P28") (pinfunction "RD4_P28") (pintype "bidirectional"))
      (node (ref "U3_TMS_RAM") (pin "2") (pinfunction "DQ1_2") (pintype "bidirectional"))
    )
    (net (code "82") (name "Net-(U2_VDP-RD5)") (class "Default")
      (node (ref "U2_VDP") (pin "P27") (pinfunction "RD5_P27") (pintype "bidirectional"))
      (node (ref "U3_TMS_RAM") (pin "3") (pinfunction "DQ2_3") (pintype "bidirectional"))
    )
    (net (code "83") (name "Net-(U2_VDP-RD6)") (class "Default")
      (node (ref "U2_VDP") (pin "P26") (pinfunction "RD6_P26") (pintype "bidirectional"))
      (node (ref "U3_TMS_RAM") (pin "15") (pinfunction "DQ3_15") (pintype "bidirectional"))
    )
    (net (code "84") (name "Net-(U2_VDP-RD7)") (class "Default")
      (node (ref "U2_VDP") (pin "P25") (pinfunction "RD7_P25") (pintype "bidirectional"))
      (node (ref "U3_TMS_RAM") (pin "17") (pinfunction "DQ4_17") (pintype "bidirectional"))
    )
    (net (code "85") (name "Net-(U2_VDP-VDD)") (class "Default")
      (node (ref "C16") (pin "+") (pinfunction "+_+") (pintype "passive"))
      (node (ref "L1") (pin "1") (pinfunction "1_1") (pintype "passive"))
      (node (ref "Q2") (pin "C") (pinfunction "C_C") (pintype "passive"))
      (node (ref "U2_VDP") (pin "P33") (pinfunction "VDD_P33") (pintype "bidirectional"))
    )
    (net (code "86") (name "Net-(U4_SND2-READY)") (class "Default")
      (node (ref "J2-WAITS") (pin "3") (pinfunction "3_3") (pintype "passive"))
      (node (ref "U4_SND2") (pin "P4") (pinfunction "READY_P4") (pintype "bidirectional"))
    )
    (net (code "87") (name "Net-(U4_SND2-SNDOUT)") (class "Default")
      (node (ref "C1") (pin "+") (pinfunction "+_+") (pintype "passive"))
      (node (ref "U4_SND2") (pin "P7") (pinfunction "SNDOUT_P7") (pintype "bidirectional"))
    )
    (net (code "88") (name "Net-(U5_SND3-READY)") (class "Default")
      (node (ref "J2-WAITS") (pin "7") (pinfunction "7_7") (pintype "passive"))
      (node (ref "U5_SND3") (pin "P4") (pinfunction "READY_P4") (pintype "bidirectional"))
    )
    (net (code "89") (name "Net-(U5_SND3-SNDOUT)") (class "Default")
      (node (ref "C11") (pin "+") (pinfunction "+_+") (pintype "passive"))
      (node (ref "U5_SND3") (pin "P7") (pinfunction "SNDOUT_P7") (pintype "bidirectional"))
    )
    (net (code "90") (name "Net-(U6_SND4-READY)") (class "Default")
      (node (ref "J2-WAITS") (pin "2") (pinfunction "2_2") (pintype "passive"))
      (node (ref "U6_SND4") (pin "P4") (pinfunction "READY_P4") (pintype "bidirectional"))
    )
    (net (code "91") (name "Net-(U6_SND4-SNDOUT)") (class "Default")
      (node (ref "C12") (pin "+") (pinfunction "+_+") (pintype "passive"))
      (node (ref "U6_SND4") (pin "P7") (pinfunction "SNDOUT_P7") (pintype "bidirectional"))
    )
    (net (code "92") (name "Net-(U11_SND1-READY)") (class "Default")
      (node (ref "J2-WAITS") (pin "5") (pinfunction "5_5") (pintype "passive"))
      (node (ref "U11_SND1") (pin "P4") (pinfunction "READY_P4") (pintype "bidirectional"))
    )
    (net (code "93") (name "Net-(U11_SND1-SNDOUT)") (class "Default")
      (node (ref "C27") (pin "+") (pinfunction "+_+") (pintype "passive"))
      (node (ref "U11_SND1") (pin "P7") (pinfunction "SNDOUT_P7") (pintype "bidirectional"))
    )
    (net (code "94") (name "VCC") (class "Default")
      (node (ref "C10") (pin "1") (pinfunction "1_1") (pintype "passive"))
      (node (ref "C13") (pin "1") (pinfunction "1_1") (pintype "passive"))
      (node (ref "C14") (pin "1") (pinfunction "1_1") (pintype "passive"))
      (node (ref "C15") (pin "1") (pinfunction "1_1") (pintype "passive"))
      (node (ref "C2") (pin "1") (pinfunction "1_1") (pintype "passive"))
      (node (ref "C3") (pin "1") (pinfunction "1_1") (pintype "passive"))
      (node (ref "C4") (pin "1") (pinfunction "1_1") (pintype "passive"))
      (node (ref "C5") (pin "1") (pinfunction "1_1") (pintype "passive"))
      (node (ref "C6") (pin "1") (pinfunction "1_1") (pintype "passive"))
      (node (ref "C7") (pin "1") (pinfunction "1_1") (pintype "passive"))
      (node (ref "C8") (pin "1") (pinfunction "1_1") (pintype "passive"))
      (node (ref "C9") (pin "1") (pinfunction "1_1") (pintype "passive"))
      (node (ref "IC1_JOY2_BUF") (pin "20") (pinfunction "VCC_20") (pintype "power_in"))
      (node (ref "IC2_GLU") (pin "24") (pinfunction "VCC_24") (pintype "bidirectional"))
      (node (ref "IC3") (pin "1") (pinfunction "CLR_1") (pintype "input"))
      (node (ref "IC3") (pin "10") (pinfunction "PRE_10") (pintype "input"))
      (node (ref "IC3") (pin "13") (pinfunction "CLR_13") (pintype "input"))
      (node (ref "IC3") (pin "14") (pinfunction "VCC_14") (pintype "power_in"))
      (node (ref "IC3") (pin "4") (pinfunction "PRE_4") (pintype "input"))
      (node (ref "IC8_JOY1_BUF") (pin "20") (pinfunction "VCC_20") (pintype "power_in"))
      (node (ref "IC9-74HCU04") (pin "14") (pinfunction "VCC_14") (pintype "power_in"))
      (node (ref "J2_DATA_AND_POWER_CON") (pin "1") (pinfunction "1_1") (pintype "passive"))
      (node (ref "L1") (pin "2") (pinfunction "2_2") (pintype "passive"))
      (node (ref "R12") (pin "1") (pinfunction "1_1") (pintype "passive"))
      (node (ref "R13") (pin "1") (pinfunction "1_1") (pintype "passive"))
      (node (ref "R9") (pin "2") (pinfunction "2_2") (pintype "passive"))
      (node (ref "RN1") (pin "1") (pinfunction "1_1") (pintype "passive"))
      (node (ref "U11_SND1") (pin "P16") (pinfunction "VCC_P16") (pintype "bidirectional"))
      (node (ref "U1_TMS_RAM") (pin "9") (pinfunction "VDD_9") (pintype "bidirectional"))
      (node (ref "U3_TMS_RAM") (pin "9") (pinfunction "VDD_9") (pintype "bidirectional"))
      (node (ref "U4_SND2") (pin "P16") (pinfunction "VCC_P16") (pintype "bidirectional"))
      (node (ref "U5_SND3") (pin "P16") (pinfunction "VCC_P16") (pintype "bidirectional"))
      (node (ref "U6_SND4") (pin "P16") (pinfunction "VCC_P16") (pintype "bidirectional"))
      (node (ref "Y1") (pin "1") (pinfunction "CTL_1") (pintype "passive"))
      (node (ref "Y1") (pin "8") (pinfunction "VDD_8") (pintype "power_in"))
    )
    (net (code "95") (name "unconnected-(IC2_GLU-NC-Pad1)") (class "Default")
      (node (ref "IC2_GLU") (pin "1") (pinfunction "NC_1") (pintype "bidirectional"))
    )
    (net (code "96") (name "unconnected-(IC2_GLU-NC2-Pad4)") (class "Default")
      (node (ref "IC2_GLU") (pin "4") (pinfunction "NC2_4") (pintype "bidirectional"))
    )
    (net (code "97") (name "unconnected-(IC2_GLU-NC3-Pad14)") (class "Default")
      (node (ref "IC2_GLU") (pin "14") (pinfunction "NC3_14") (pintype "bidirectional"))
    )
    (net (code "98") (name "unconnected-(IC9-74HCU04D-O-Pad8)") (class "Default")
      (node (ref "IC9-74HCU04") (pin "8") (pinfunction "O_8") (pintype "output"))
    )
    (net (code "99") (name "unconnected-(IC9-74HCU04E-O-Pad10)") (class "Default")
      (node (ref "IC9-74HCU04") (pin "10") (pinfunction "O_10") (pintype "output"))
    )
    (net (code "100") (name "unconnected-(IC9-74HCU04F-O-Pad12)") (class "Default")
      (node (ref "IC9-74HCU04") (pin "12") (pinfunction "O_12") (pintype "output"))
    )
    (net (code "101") (name "unconnected-(J1-INTERRUPTS-Pad1)") (class "Default")
      (node (ref "J1-INTERRUPTS") (pin "1") (pinfunction "1_1") (pintype "passive"))
    )
    (net (code "102") (name "unconnected-(J1-INTERRUPTS-Pad2)") (class "Default")
      (node (ref "J1-INTERRUPTS") (pin "2") (pinfunction "2_2") (pintype "passive"))
    )
    (net (code "103") (name "unconnected-(J1-INTERRUPTS-Pad4)") (class "Default")
      (node (ref "J1-INTERRUPTS") (pin "4") (pinfunction "4_4") (pintype "passive"))
    )
    (net (code "104") (name "unconnected-(J1-INTERRUPTS-Pad5)") (class "Default")
      (node (ref "J1-INTERRUPTS") (pin "5") (pinfunction "5_5") (pintype "passive"))
    )
    (net (code "105") (name "unconnected-(J1-INTERRUPTS-Pad6)") (class "Default")
      (node (ref "J1-INTERRUPTS") (pin "6") (pinfunction "6_6") (pintype "passive"))
    )
    (net (code "106") (name "unconnected-(J1-INTERRUPTS-Pad7)") (class "Default")
      (node (ref "J1-INTERRUPTS") (pin "7") (pinfunction "7_7") (pintype "passive"))
    )
    (net (code "107") (name "unconnected-(J1-INTERRUPTS-Pad8)") (class "Default")
      (node (ref "J1-INTERRUPTS") (pin "8") (pinfunction "8_8") (pintype "passive"))
    )
    (net (code "108") (name "unconnected-(J1_ADDRESS_CON-Pad9)") (class "Default")
      (node (ref "J1_ADDRESS_CON") (pin "9") (pinfunction "9_9") (pintype "passive"))
    )
    (net (code "109") (name "unconnected-(J1_ADDRESS_CON-Pad10)") (class "Default")
      (node (ref "J1_ADDRESS_CON") (pin "10") (pinfunction "10_10") (pintype "passive"))
    )
    (net (code "110") (name "unconnected-(J1_ADDRESS_CON-Pad11)") (class "Default")
      (node (ref "J1_ADDRESS_CON") (pin "11") (pinfunction "11_11") (pintype "passive"))
    )
    (net (code "111") (name "unconnected-(J1_ADDRESS_CON-Pad12)") (class "Default")
      (node (ref "J1_ADDRESS_CON") (pin "12") (pinfunction "12_12") (pintype "passive"))
    )
    (net (code "112") (name "unconnected-(J1_ADDRESS_CON-Pad13)") (class "Default")
      (node (ref "J1_ADDRESS_CON") (pin "13") (pinfunction "13_13") (pintype "passive"))
    )
    (net (code "113") (name "unconnected-(J1_ADDRESS_CON-Pad14)") (class "Default")
      (node (ref "J1_ADDRESS_CON") (pin "14") (pinfunction "14_14") (pintype "passive"))
    )
    (net (code "114") (name "unconnected-(J1_ADDRESS_CON-Pad15)") (class "Default")
      (node (ref "J1_ADDRESS_CON") (pin "15") (pinfunction "15_15") (pintype "passive"))
    )
    (net (code "115") (name "unconnected-(J1_ADDRESS_CON-Pad16)") (class "Default")
      (node (ref "J1_ADDRESS_CON") (pin "16") (pinfunction "16_16") (pintype "passive"))
    )
    (net (code "116") (name "unconnected-(J1_ADDRESS_CON-Pad19)") (class "Default")
      (node (ref "J1_ADDRESS_CON") (pin "19") (pinfunction "19_19") (pintype "passive"))
    )
    (net (code "117") (name "unconnected-(J1_ADDRESS_CON-Pad20)") (class "Default")
      (node (ref "J1_ADDRESS_CON") (pin "20") (pinfunction "20_20") (pintype "passive"))
    )
    (net (code "118") (name "unconnected-(J2-WAITS-Pad1)") (class "Default")
      (node (ref "J2-WAITS") (pin "1") (pinfunction "1_1") (pintype "passive"))
    )
    (net (code "119") (name "unconnected-(J2-WAITS-Pad4)") (class "Default")
      (node (ref "J2-WAITS") (pin "4") (pinfunction "4_4") (pintype "passive"))
    )
    (net (code "120") (name "unconnected-(J2-WAITS-Pad6)") (class "Default")
      (node (ref "J2-WAITS") (pin "6") (pinfunction "6_6") (pintype "passive"))
    )
    (net (code "121") (name "unconnected-(J2-WAITS-Pad8)") (class "Default")
      (node (ref "J2-WAITS") (pin "8") (pinfunction "8_8") (pintype "passive"))
    )
    (net (code "122") (name "unconnected-(J2_DATA_AND_POWER_CON-Pad3)") (class "Default")
      (node (ref "J2_DATA_AND_POWER_CON") (pin "3") (pinfunction "3_3") (pintype "passive"))
    )
    (net (code "123") (name "unconnected-(J2_DATA_AND_POWER_CON-Pad4)") (class "Default")
      (node (ref "J2_DATA_AND_POWER_CON") (pin "4") (pinfunction "4_4") (pintype "passive"))
    )
    (net (code "124") (name "unconnected-(J2_DATA_AND_POWER_CON-Pad5)") (class "Default")
      (node (ref "J2_DATA_AND_POWER_CON") (pin "5") (pinfunction "5_5") (pintype "passive"))
    )
    (net (code "125") (name "unconnected-(J2_DATA_AND_POWER_CON-Pad6)") (class "Default")
      (node (ref "J2_DATA_AND_POWER_CON") (pin "6") (pinfunction "6_6") (pintype "passive"))
    )
    (net (code "126") (name "unconnected-(J2_DATA_AND_POWER_CON-Pad7)") (class "Default")
      (node (ref "J2_DATA_AND_POWER_CON") (pin "7") (pinfunction "7_7") (pintype "passive"))
    )
    (net (code "127") (name "unconnected-(J2_DATA_AND_POWER_CON-Pad9)") (class "Default")
      (node (ref "J2_DATA_AND_POWER_CON") (pin "9") (pinfunction "9_9") (pintype "passive"))
    )
    (net (code "128") (name "unconnected-(J2_DATA_AND_POWER_CON-Pad10)") (class "Default")
      (node (ref "J2_DATA_AND_POWER_CON") (pin "10") (pinfunction "10_10") (pintype "passive"))
    )
    (net (code "129") (name "unconnected-(J2_DATA_AND_POWER_CON-Pad11)") (class "Default")
      (node (ref "J2_DATA_AND_POWER_CON") (pin "11") (pinfunction "11_11") (pintype "passive"))
    )
    (net (code "130") (name "unconnected-(J2_DATA_AND_POWER_CON-Pad12)") (class "Default")
      (node (ref "J2_DATA_AND_POWER_CON") (pin "12") (pinfunction "12_12") (pintype "passive"))
    )
    (net (code "131") (name "unconnected-(JOYSTICK1-Pad1)") (class "Default")
      (node (ref "JOYSTICK1") (pin "1") (pinfunction "1_1") (pintype "passive"))
    )
    (net (code "132") (name "unconnected-(JOYSTICK1-Pad6)") (class "Default")
      (node (ref "JOYSTICK1") (pin "6") (pinfunction "6_6") (pintype "passive"))
    )
    (net (code "133") (name "unconnected-(JOYSTICK1-Pad8)") (class "Default")
      (node (ref "JOYSTICK1") (pin "8") (pinfunction "8_8") (pintype "passive"))
    )
    (net (code "134") (name "unconnected-(JOYSTICK2-Pad1)") (class "Default")
      (node (ref "JOYSTICK2") (pin "1") (pinfunction "1_1") (pintype "passive"))
    )
    (net (code "135") (name "unconnected-(JOYSTICK2-Pad6)") (class "Default")
      (node (ref "JOYSTICK2") (pin "6") (pinfunction "6_6") (pintype "passive"))
    )
    (net (code "136") (name "unconnected-(JOYSTICK2-Pad8)") (class "Default")
      (node (ref "JOYSTICK2") (pin "8") (pinfunction "8_8") (pintype "passive"))
    )
    (net (code "137") (name "unconnected-(R8-A-Pad1)") (class "Default")
      (node (ref "R8") (pin "1") (pinfunction "A_1") (pintype "passive"))
    )
    (net (code "138") (name "unconnected-(U2_VDP-EXTVDP-PadP35)") (class "Default")
      (node (ref "U2_VDP") (pin "P35") (pinfunction "EXTVDP_P35") (pintype "bidirectional"))
    )
    (net (code "139") (name "unconnected-(U2_VDP-NC-PadP37)") (class "Default")
      (node (ref "U2_VDP") (pin "P37") (pinfunction "NC_P37") (pintype "bidirectional"))
    )
    (net (code "140") (name "unconnected-(U4_SND2-NC-PadP9)") (class "Default")
      (node (ref "U4_SND2") (pin "P9") (pinfunction "NC_P9") (pintype "bidirectional"))
    )
    (net (code "141") (name "unconnected-(U5_SND3-NC-PadP9)") (class "Default")
      (node (ref "U5_SND3") (pin "P9") (pinfunction "NC_P9") (pintype "bidirectional"))
    )
    (net (code "142") (name "unconnected-(U6_SND4-NC-PadP9)") (class "Default")
      (node (ref "U6_SND4") (pin "P9") (pinfunction "NC_P9") (pintype "bidirectional"))
    )
    (net (code "143") (name "unconnected-(U11_SND1-NC-PadP9)") (class "Default")
      (node (ref "U11_SND1") (pin "P9") (pinfunction "NC_P9") (pintype "bidirectional"))
    )
  )
)
